# m11tcp.net
KiCad netlist of a schematic drawn in Altium Designer
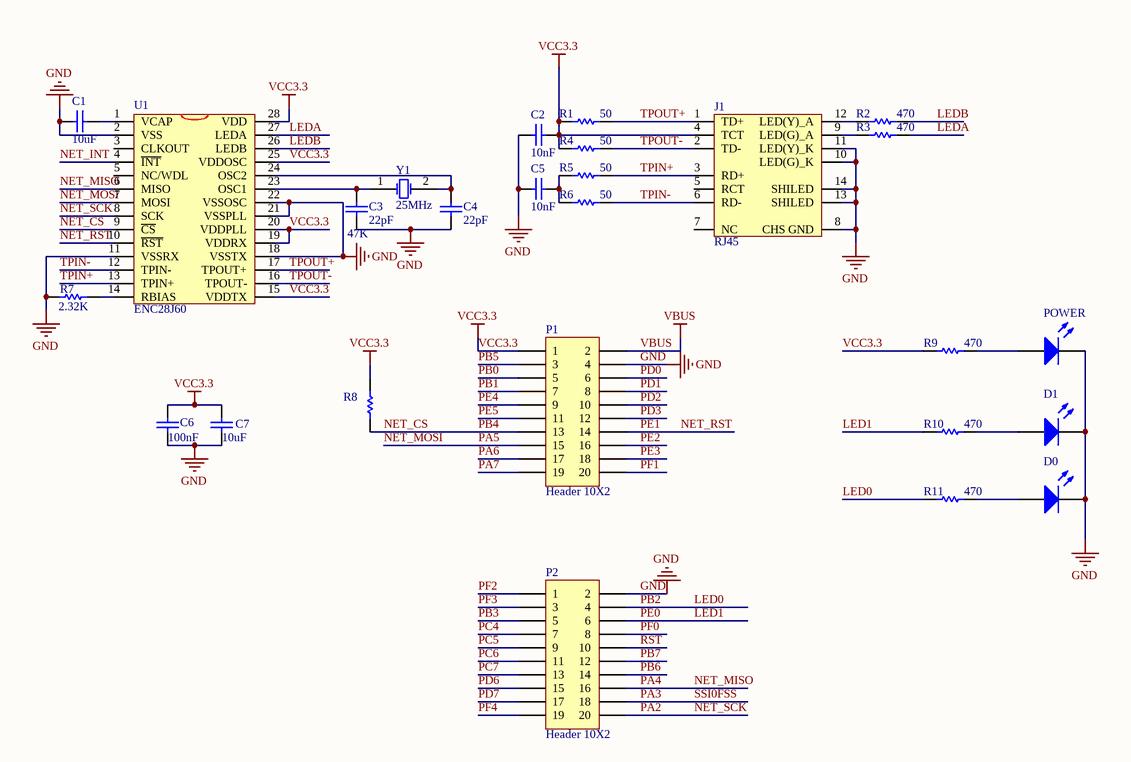
[diagram p0: m11tcp.SchDoc]

(export (version "E")
  (design (tool "Eeschema 10.0.6"))
  (components
    (comp (ref "C1")
      (value "10uF")
      (footprint "CAP_0603")
      (description "Capacitor (Semiconductor SIM Model)")
      (fields (field (name "Comment") "Cap Semi") (field (name "PUBLISHER") "Altium Limited"))
      (libsource (lib "Miscellaneous Devices") (part "Cap Semi"))
    )
    (comp (ref "C2")
      (value "10nF")
      (footprint "CAP_0603")
      (description "Capacitor (Semiconductor SIM Model)")
      (fields (field (name "Comment") "Cap Semi") (field (name "PUBLISHER") "Altium Limited"))
      (libsource (lib "Miscellaneous Devices") (part "Cap Semi"))
    )
    (comp (ref "C3")
      (value "22pF")
      (footprint "CAP_0603")
      (description "Capacitor (Semiconductor SIM Model)")
      (fields (field (name "Comment") "Cap Semi") (field (name "PUBLISHER") "Altium Limited"))
      (libsource (lib "Miscellaneous Devices") (part "Cap Semi"))
    )
    (comp (ref "C4")
      (value "22pF")
      (footprint "CAP_0603")
      (description "Capacitor (Semiconductor SIM Model)")
      (fields (field (name "Comment") "Cap Semi") (field (name "PUBLISHER") "Altium Limited"))
      (libsource (lib "Miscellaneous Devices") (part "Cap Semi"))
    )
    (comp (ref "C5")
      (value "10nF")
      (footprint "CAP_0603")
      (description "Capacitor (Semiconductor SIM Model)")
      (fields (field (name "Comment") "Cap Semi") (field (name "PUBLISHER") "Altium Limited"))
      (libsource (lib "Miscellaneous Devices") (part "Cap Semi"))
    )
    (comp (ref "C6")
      (value "100nF")
      (footprint "CAP_0603")
      (description "Capacitor (Semiconductor SIM Model)")
      (fields (field (name "Comment") "Cap Semi") (field (name "PUBLISHER") "Altium Limited"))
      (libsource (lib "Miscellaneous Devices") (part "Cap Semi"))
    )
    (comp (ref "C7")
      (value "10uF")
      (footprint "CAP_0603")
      (description "Capacitor (Semiconductor SIM Model)")
      (fields (field (name "Comment") "Cap Semi") (field (name "PUBLISHER") "Altium Limited"))
      (libsource (lib "Miscellaneous Devices") (part "Cap Semi"))
    )
    (comp (ref "D0")
      (value "LED2")
      (footprint "LED_0603_RED")
      (description "Typical RED, GREEN, YELLOW, AMBER GaAs LED")
      (fields (field (name "PUBLISHER") "Altium Limited"))
      (libsource (lib "Miscellaneous Devices") (part "LED2"))
    )
    (comp (ref "D1")
      (value "LED2")
      (footprint "LED_0603_RED")
      (description "Typical RED, GREEN, YELLOW, AMBER GaAs LED")
      (fields (field (name "PUBLISHER") "Altium Limited"))
      (libsource (lib "Miscellaneous Devices") (part "LED2"))
    )
    (comp (ref "J1")
      (value "RJ45")
      (footprint "HR911105A")
      (libsource (lib "ENC28J60网络模块封装库") (part "HR911105"))
    )
    (comp (ref "P1")
      (value "Header 10X2")
      (footprint "HDR2X10")
      (description "Header, 10-Pin, Dual row")
      (fields (field (name "PUBLISHER") "Altium Limited"))
      (libsource (lib "Miscellaneous Connectors") (part "Header 10X2"))
    )
    (comp (ref "P2")
      (value "Header 10X2")
      (footprint "HDR2X10")
      (description "Header, 10-Pin, Dual row")
      (fields (field (name "PUBLISHER") "Altium Limited"))
      (libsource (lib "Miscellaneous Connectors") (part "Header 10X2"))
    )
    (comp (ref "POWER")
      (value "LED2")
      (footprint "LED_0603_RED")
      (description "Typical RED, GREEN, YELLOW, AMBER GaAs LED")
      (fields (field (name "PUBLISHER") "Altium Limited"))
      (libsource (lib "Miscellaneous Devices") (part "LED2"))
    )
    (comp (ref "R1")
      (value "50")
      (footprint "RES_0603")
      (description "Semiconductor Resistor")
      (fields (field (name "Comment") "Res Semi") (field (name "PUBLISHER") "Altium Limited"))
      (libsource (lib "Miscellaneous Devices") (part "Res Semi"))
    )
    (comp (ref "R2")
      (value "470")
      (footprint "RES_0603")
      (description "Semiconductor Resistor")
      (fields (field (name "Comment") "Res Semi") (field (name "PUBLISHER") "Altium Limited"))
      (libsource (lib "Miscellaneous Devices") (part "Res Semi"))
    )
    (comp (ref "R3")
      (value "470")
      (footprint "RES_0603")
      (description "Semiconductor Resistor")
      (fields (field (name "Comment") "Res Semi") (field (name "PUBLISHER") "Altium Limited"))
      (libsource (lib "Miscellaneous Devices") (part "Res Semi"))
    )
    (comp (ref "R4")
      (value "50")
      (footprint "RES_0603")
      (description "Semiconductor Resistor")
      (fields (field (name "Comment") "Res Semi") (field (name "PUBLISHER") "Altium Limited"))
      (libsource (lib "Miscellaneous Devices") (part "Res Semi"))
    )
    (comp (ref "R5")
      (value "50")
      (footprint "RES_0603")
      (description "Semiconductor Resistor")
      (fields (field (name "Comment") "Res Semi") (field (name "PUBLISHER") "Altium Limited"))
      (libsource (lib "Miscellaneous Devices") (part "Res Semi"))
    )
    (comp (ref "R6")
      (value "50")
      (footprint "RES_0603")
      (description "Semiconductor Resistor")
      (fields (field (name "Comment") "Res Semi") (field (name "PUBLISHER") "Altium Limited"))
      (libsource (lib "Miscellaneous Devices") (part "Res Semi"))
    )
    (comp (ref "R7")
      (value "2.32K")
      (footprint "RES_0603")
      (description "Semiconductor Resistor")
      (fields (field (name "Comment") "Res Semi") (field (name "PUBLISHER") "Altium Limited"))
      (libsource (lib "Miscellaneous Devices") (part "Res Semi"))
    )
    (comp (ref "R8")
      (value "47K")
      (footprint "RES_0603")
      (description "Semiconductor Resistor")
      (fields (field (name "Comment") "Res Semi") (field (name "PUBLISHER") "Altium Limited"))
      (libsource (lib "Miscellaneous Devices") (part "Res Semi"))
    )
    (comp (ref "R9")
      (value "470")
      (footprint "RES_0603")
      (description "Semiconductor Resistor")
      (fields (field (name "Comment") "Res Semi") (field (name "PUBLISHER") "Altium Limited"))
      (libsource (lib "Miscellaneous Devices") (part "Res Semi"))
    )
    (comp (ref "R10")
      (value "470")
      (footprint "RES_0603")
      (description "Semiconductor Resistor")
      (fields (field (name "Comment") "Res Semi") (field (name "PUBLISHER") "Altium Limited"))
      (libsource (lib "Miscellaneous Devices") (part "Res Semi"))
    )
    (comp (ref "R11")
      (value "470")
      (footprint "RES_0603")
      (description "Semiconductor Resistor")
      (fields (field (name "Comment") "Res Semi") (field (name "PUBLISHER") "Altium Limited"))
      (libsource (lib "Miscellaneous Devices") (part "Res Semi"))
    )
    (comp (ref "U1")
      (value "ENC28J60")
      (footprint "SSOP28")
      (libsource (lib "ENC28J60网络模块封装库") (part "ENC28J60"))
    )
    (comp (ref "Y1")
      (value "25MHz")
      (footprint "XTAL_US")
      (description "Crystal Oscillator")
      (fields (field (name "PUBLISHER") "Altium Limited"))
      (libsource (lib "ENC28J60网络模块封装库") (part "XTAL"))
    )
  )
  (nets
    (net (code "1") (name "/LED0") (class "Default")
      (node (ref "P2") (pin "4") (pinfunction "4_4") (pintype "passive"))
      (node (ref "R11") (pin "1") (pinfunction "1_1") (pintype "passive"))
    )
    (net (code "2") (name "/LED1") (class "Default")
      (node (ref "P2") (pin "6") (pinfunction "6_6") (pintype "passive"))
      (node (ref "R10") (pin "1") (pinfunction "1_1") (pintype "passive"))
    )
    (net (code "3") (name "/LEDA") (class "Default")
      (node (ref "R3") (pin "2") (pinfunction "2_2") (pintype "passive"))
      (node (ref "U1") (pin "27") (pinfunction "LEDA_27") (pintype "passive"))
    )
    (net (code "4") (name "/LEDB") (class "Default")
      (node (ref "R2") (pin "2") (pinfunction "2_2") (pintype "passive"))
      (node (ref "U1") (pin "26") (pinfunction "LEDB_26") (pintype "passive"))
    )
    (net (code "5") (name "/NET_CS") (class "Default")
      (node (ref "P1") (pin "13") (pinfunction "13_13") (pintype "passive"))
      (node (ref "R8") (pin "1") (pinfunction "1_1") (pintype "passive"))
      (node (ref "U1") (pin "9") (pinfunction "~{CS}_9") (pintype "passive"))
    )
    (net (code "6") (name "/NET_INT") (class "Default")
      (node (ref "U1") (pin "4") (pinfunction "~{INT}_4") (pintype "passive"))
    )
    (net (code "7") (name "/NET_MISO") (class "Default")
      (node (ref "P2") (pin "16") (pinfunction "16_16") (pintype "passive"))
      (node (ref "U1") (pin "6") (pinfunction "MISO_6") (pintype "passive"))
    )
    (net (code "8") (name "/NET_MOSI") (class "Default")
      (node (ref "P1") (pin "15") (pinfunction "15_15") (pintype "passive"))
      (node (ref "U1") (pin "7") (pinfunction "MOSI_7") (pintype "passive"))
    )
    (net (code "9") (name "/NET_RST") (class "Default")
      (node (ref "P1") (pin "14") (pinfunction "14_14") (pintype "passive"))
      (node (ref "U1") (pin "10") (pinfunction "~{RST}_10") (pintype "passive"))
    )
    (net (code "10") (name "/NET_SCK") (class "Default")
      (node (ref "P2") (pin "20") (pinfunction "20_20") (pintype "passive"))
      (node (ref "U1") (pin "8") (pinfunction "SCK_8") (pintype "passive"))
    )
    (net (code "11") (name "/PA3") (class "Default")
      (node (ref "P2") (pin "18") (pinfunction "18_18") (pintype "passive"))
    )
    (net (code "12") (name "/PA6") (class "Default")
      (node (ref "P1") (pin "17") (pinfunction "17_17") (pintype "passive"))
    )
    (net (code "13") (name "/PA7") (class "Default")
      (node (ref "P1") (pin "19") (pinfunction "19_19") (pintype "passive"))
    )
    (net (code "14") (name "/PB0") (class "Default")
      (node (ref "P1") (pin "5") (pinfunction "5_5") (pintype "passive"))
    )
    (net (code "15") (name "/PB1") (class "Default")
      (node (ref "P1") (pin "7") (pinfunction "7_7") (pintype "passive"))
    )
    (net (code "16") (name "/PB3") (class "Default")
      (node (ref "P2") (pin "5") (pinfunction "5_5") (pintype "passive"))
    )
    (net (code "17") (name "/PB5") (class "Default")
      (node (ref "P1") (pin "3") (pinfunction "3_3") (pintype "passive"))
    )
    (net (code "18") (name "/PB6") (class "Default")
      (node (ref "P2") (pin "14") (pinfunction "14_14") (pintype "passive"))
    )
    (net (code "19") (name "/PB7") (class "Default")
      (node (ref "P2") (pin "12") (pinfunction "12_12") (pintype "passive"))
    )
    (net (code "20") (name "/PC4") (class "Default")
      (node (ref "P2") (pin "7") (pinfunction "7_7") (pintype "passive"))
    )
    (net (code "21") (name "/PC5") (class "Default")
      (node (ref "P2") (pin "9") (pinfunction "9_9") (pintype "passive"))
    )
    (net (code "22") (name "/PC6") (class "Default")
      (node (ref "P2") (pin "11") (pinfunction "11_11") (pintype "passive"))
    )
    (net (code "23") (name "/PC7") (class "Default")
      (node (ref "P2") (pin "13") (pinfunction "13_13") (pintype "passive"))
    )
    (net (code "24") (name "/PD0") (class "Default")
      (node (ref "P1") (pin "6") (pinfunction "6_6") (pintype "passive"))
    )
    (net (code "25") (name "/PD1") (class "Default")
      (node (ref "P1") (pin "8") (pinfunction "8_8") (pintype "passive"))
    )
    (net (code "26") (name "/PD2") (class "Default")
      (node (ref "P1") (pin "10") (pinfunction "10_10") (pintype "passive"))
    )
    (net (code "27") (name "/PD3") (class "Default")
      (node (ref "P1") (pin "12") (pinfunction "12_12") (pintype "passive"))
    )
    (net (code "28") (name "/PD6") (class "Default")
      (node (ref "P2") (pin "15") (pinfunction "15_15") (pintype "passive"))
    )
    (net (code "29") (name "/PD7") (class "Default")
      (node (ref "P2") (pin "17") (pinfunction "17_17") (pintype "passive"))
    )
    (net (code "30") (name "/PE2") (class "Default")
      (node (ref "P1") (pin "16") (pinfunction "16_16") (pintype "passive"))
    )
    (net (code "31") (name "/PE3") (class "Default")
      (node (ref "P1") (pin "18") (pinfunction "18_18") (pintype "passive"))
    )
    (net (code "32") (name "/PE4") (class "Default")
      (node (ref "P1") (pin "9") (pinfunction "9_9") (pintype "passive"))
    )
    (net (code "33") (name "/PE5") (class "Default")
      (node (ref "P1") (pin "11") (pinfunction "11_11") (pintype "passive"))
    )
    (net (code "34") (name "/PF0") (class "Default")
      (node (ref "P2") (pin "8") (pinfunction "8_8") (pintype "passive"))
    )
    (net (code "35") (name "/PF1") (class "Default")
      (node (ref "P1") (pin "20") (pinfunction "20_20") (pintype "passive"))
    )
    (net (code "36") (name "/PF2") (class "Default")
      (node (ref "P2") (pin "1") (pinfunction "1_1") (pintype "passive"))
    )
    (net (code "37") (name "/PF3") (class "Default")
      (node (ref "P2") (pin "3") (pinfunction "3_3") (pintype "passive"))
    )
    (net (code "38") (name "/PF4") (class "Default")
      (node (ref "P2") (pin "19") (pinfunction "19_19") (pintype "passive"))
    )
    (net (code "39") (name "/RST") (class "Default")
      (node (ref "P2") (pin "10") (pinfunction "10_10") (pintype "passive"))
    )
    (net (code "40") (name "/TPIN+") (class "Default")
      (node (ref "J1") (pin "3") (pinfunction "RD+_3") (pintype "passive"))
      (node (ref "R5") (pin "2") (pinfunction "2_2") (pintype "passive"))
      (node (ref "U1") (pin "13") (pinfunction "TPIN+_13") (pintype "passive"))
    )
    (net (code "41") (name "/TPIN-") (class "Default")
      (node (ref "J1") (pin "6") (pinfunction "RD-_6") (pintype "passive"))
      (node (ref "R6") (pin "2") (pinfunction "2_2") (pintype "passive"))
      (node (ref "U1") (pin "12") (pinfunction "TPIN-_12") (pintype "passive"))
    )
    (net (code "42") (name "/TPOUT+") (class "Default")
      (node (ref "J1") (pin "1") (pinfunction "TD+_1") (pintype "passive"))
      (node (ref "R1") (pin "2") (pinfunction "2_2") (pintype "passive"))
      (node (ref "U1") (pin "17") (pinfunction "TPOUT+_17") (pintype "passive"))
    )
    (net (code "43") (name "/TPOUT-") (class "Default")
      (node (ref "J1") (pin "2") (pinfunction "TD-_2") (pintype "passive"))
      (node (ref "R4") (pin "2") (pinfunction "2_2") (pintype "passive"))
      (node (ref "U1") (pin "16") (pinfunction "TPOUT-_16") (pintype "passive"))
    )
    (net (code "44") (name "GND") (class "Default")
      (node (ref "C1") (pin "1") (pinfunction "1_1") (pintype "passive"))
      (node (ref "C2") (pin "1") (pinfunction "1_1") (pintype "passive"))
      (node (ref "C3") (pin "1") (pinfunction "1_1") (pintype "passive"))
      (node (ref "C4") (pin "1") (pinfunction "1_1") (pintype "passive"))
      (node (ref "C5") (pin "1") (pinfunction "1_1") (pintype "passive"))
      (node (ref "C6") (pin "1") (pinfunction "1_1") (pintype "passive"))
      (node (ref "C7") (pin "1") (pinfunction "1_1") (pintype "passive"))
      (node (ref "D0") (pin "2") (pinfunction "K_2") (pintype "passive"))
      (node (ref "D1") (pin "2") (pinfunction "K_2") (pintype "passive"))
      (node (ref "J1") (pin "10") (pinfunction "LED(G)_K_10") (pintype "passive"))
      (node (ref "J1") (pin "11") (pinfunction "LED(Y)_K_11") (pintype "passive"))
      (node (ref "J1") (pin "13") (pinfunction "SHILED_13") (pintype "passive"))
      (node (ref "J1") (pin "14") (pinfunction "SHILED_14") (pintype "passive"))
      (node (ref "J1") (pin "8") (pinfunction "CHS_GND_8") (pintype "passive"))
      (node (ref "P1") (pin "4") (pinfunction "4_4") (pintype "passive"))
      (node (ref "P2") (pin "2") (pinfunction "2_2") (pintype "passive"))
      (node (ref "POWER") (pin "2") (pinfunction "K_2") (pintype "passive"))
      (node (ref "R7") (pin "1") (pinfunction "1_1") (pintype "passive"))
      (node (ref "U1") (pin "11") (pinfunction "VSSRX_11") (pintype "passive"))
      (node (ref "U1") (pin "18") (pinfunction "VSSTX_18") (pintype "passive"))
      (node (ref "U1") (pin "2") (pinfunction "VSS_2") (pintype "passive"))
      (node (ref "U1") (pin "21") (pinfunction "VSSPLL_21") (pintype "passive"))
      (node (ref "U1") (pin "22") (pinfunction "VSSOSC_22") (pintype "passive"))
    )
    (net (code "45") (name "Net-(C5-Pad2)") (class "Default")
      (node (ref "C5") (pin "2") (pinfunction "2_2") (pintype "passive"))
      (node (ref "R5") (pin "1") (pinfunction "1_1") (pintype "passive"))
      (node (ref "R6") (pin "1") (pinfunction "1_1") (pintype "passive"))
    )
    (net (code "46") (name "Net-(D0-A)") (class "Default")
      (node (ref "D0") (pin "1") (pinfunction "A_1") (pintype "passive"))
      (node (ref "R11") (pin "2") (pinfunction "2_2") (pintype "passive"))
    )
    (net (code "47") (name "Net-(D1-A)") (class "Default")
      (node (ref "D1") (pin "1") (pinfunction "A_1") (pintype "passive"))
      (node (ref "R10") (pin "2") (pinfunction "2_2") (pintype "passive"))
    )
    (net (code "48") (name "Net-(J1-LED(G)_A)") (class "Default")
      (node (ref "J1") (pin "9") (pinfunction "LED(G)_A_9") (pintype "passive"))
      (node (ref "R3") (pin "1") (pinfunction "1_1") (pintype "passive"))
    )
    (net (code "49") (name "Net-(J1-LED(Y)_A)") (class "Default")
      (node (ref "J1") (pin "12") (pinfunction "LED(Y)_A_12") (pintype "passive"))
      (node (ref "R2") (pin "1") (pinfunction "1_1") (pintype "passive"))
    )
    (net (code "50") (name "Net-(POWER-A)") (class "Default")
      (node (ref "POWER") (pin "1") (pinfunction "A_1") (pintype "passive"))
      (node (ref "R9") (pin "2") (pinfunction "2_2") (pintype "passive"))
    )
    (net (code "51") (name "Net-(U1-OSC1)") (class "Default")
      (node (ref "C3") (pin "2") (pinfunction "2_2") (pintype "passive"))
      (node (ref "U1") (pin "23") (pinfunction "OSC1_23") (pintype "passive"))
      (node (ref "Y1") (pin "1") (pinfunction "OSC1_1") (pintype "passive"))
    )
    (net (code "52") (name "Net-(U1-OSC2)") (class "Default")
      (node (ref "C4") (pin "2") (pinfunction "2_2") (pintype "passive"))
      (node (ref "U1") (pin "24") (pinfunction "OSC2_24") (pintype "passive"))
      (node (ref "Y1") (pin "2") (pinfunction "OSC2_2") (pintype "passive"))
    )
    (net (code "53") (name "Net-(U1-RBIAS)") (class "Default")
      (node (ref "R7") (pin "2") (pinfunction "2_2") (pintype "passive"))
      (node (ref "U1") (pin "14") (pinfunction "RBIAS_14") (pintype "passive"))
    )
    (net (code "54") (name "Net-(U1-VCAP)") (class "Default")
      (node (ref "C1") (pin "2") (pinfunction "2_2") (pintype "passive"))
      (node (ref "U1") (pin "1") (pinfunction "VCAP_1") (pintype "passive"))
    )
    (net (code "55") (name "VBUS") (class "Default")
      (node (ref "P1") (pin "2") (pinfunction "2_2") (pintype "passive"))
    )
    (net (code "56") (name "VCC3.3") (class "Default")
      (node (ref "C2") (pin "2") (pinfunction "2_2") (pintype "passive"))
      (node (ref "C6") (pin "2") (pinfunction "2_2") (pintype "passive"))
      (node (ref "C7") (pin "2") (pinfunction "2_2") (pintype "passive"))
      (node (ref "J1") (pin "4") (pinfunction "TCT_4") (pintype "passive"))
      (node (ref "P1") (pin "1") (pinfunction "1_1") (pintype "passive"))
      (node (ref "R1") (pin "1") (pinfunction "1_1") (pintype "passive"))
      (node (ref "R4") (pin "1") (pinfunction "1_1") (pintype "passive"))
      (node (ref "R8") (pin "2") (pinfunction "2_2") (pintype "passive"))
      (node (ref "R9") (pin "1") (pinfunction "1_1") (pintype "passive"))
      (node (ref "U1") (pin "15") (pinfunction "VDDTX_15") (pintype "passive"))
      (node (ref "U1") (pin "19") (pinfunction "VDDRX_19") (pintype "passive"))
      (node (ref "U1") (pin "20") (pinfunction "VDDPLL_20") (pintype "passive"))
      (node (ref "U1") (pin "25") (pinfunction "VDDOSC_25") (pintype "passive"))
      (node (ref "U1") (pin "28") (pinfunction "VDD_28") (pintype "passive"))
    )
    (net (code "57") (name "unconnected-(J1-NC-Pad7)") (class "Default")
      (node (ref "J1") (pin "7") (pinfunction "NC_7") (pintype "passive"))
    )
    (net (code "58") (name "unconnected-(J1-RCT-Pad5)") (class "Default")
      (node (ref "J1") (pin "5") (pinfunction "RCT_5") (pintype "passive"))
    )
    (net (code "59") (name "unconnected-(U1-CLKOUT-Pad3)") (class "Default")
      (node (ref "U1") (pin "3") (pinfunction "CLKOUT_3") (pintype "passive"))
    )
    (net (code "60") (name "unconnected-(U1-NC{slash}WDL-Pad5)") (class "Default")
      (node (ref "U1") (pin "5") (pinfunction "NC/WDL_5") (pintype "passive"))
    )
  )
)
